# Platine_Diplomarbeit.net
KiCad netlist of a schematic drawn in EAGLE
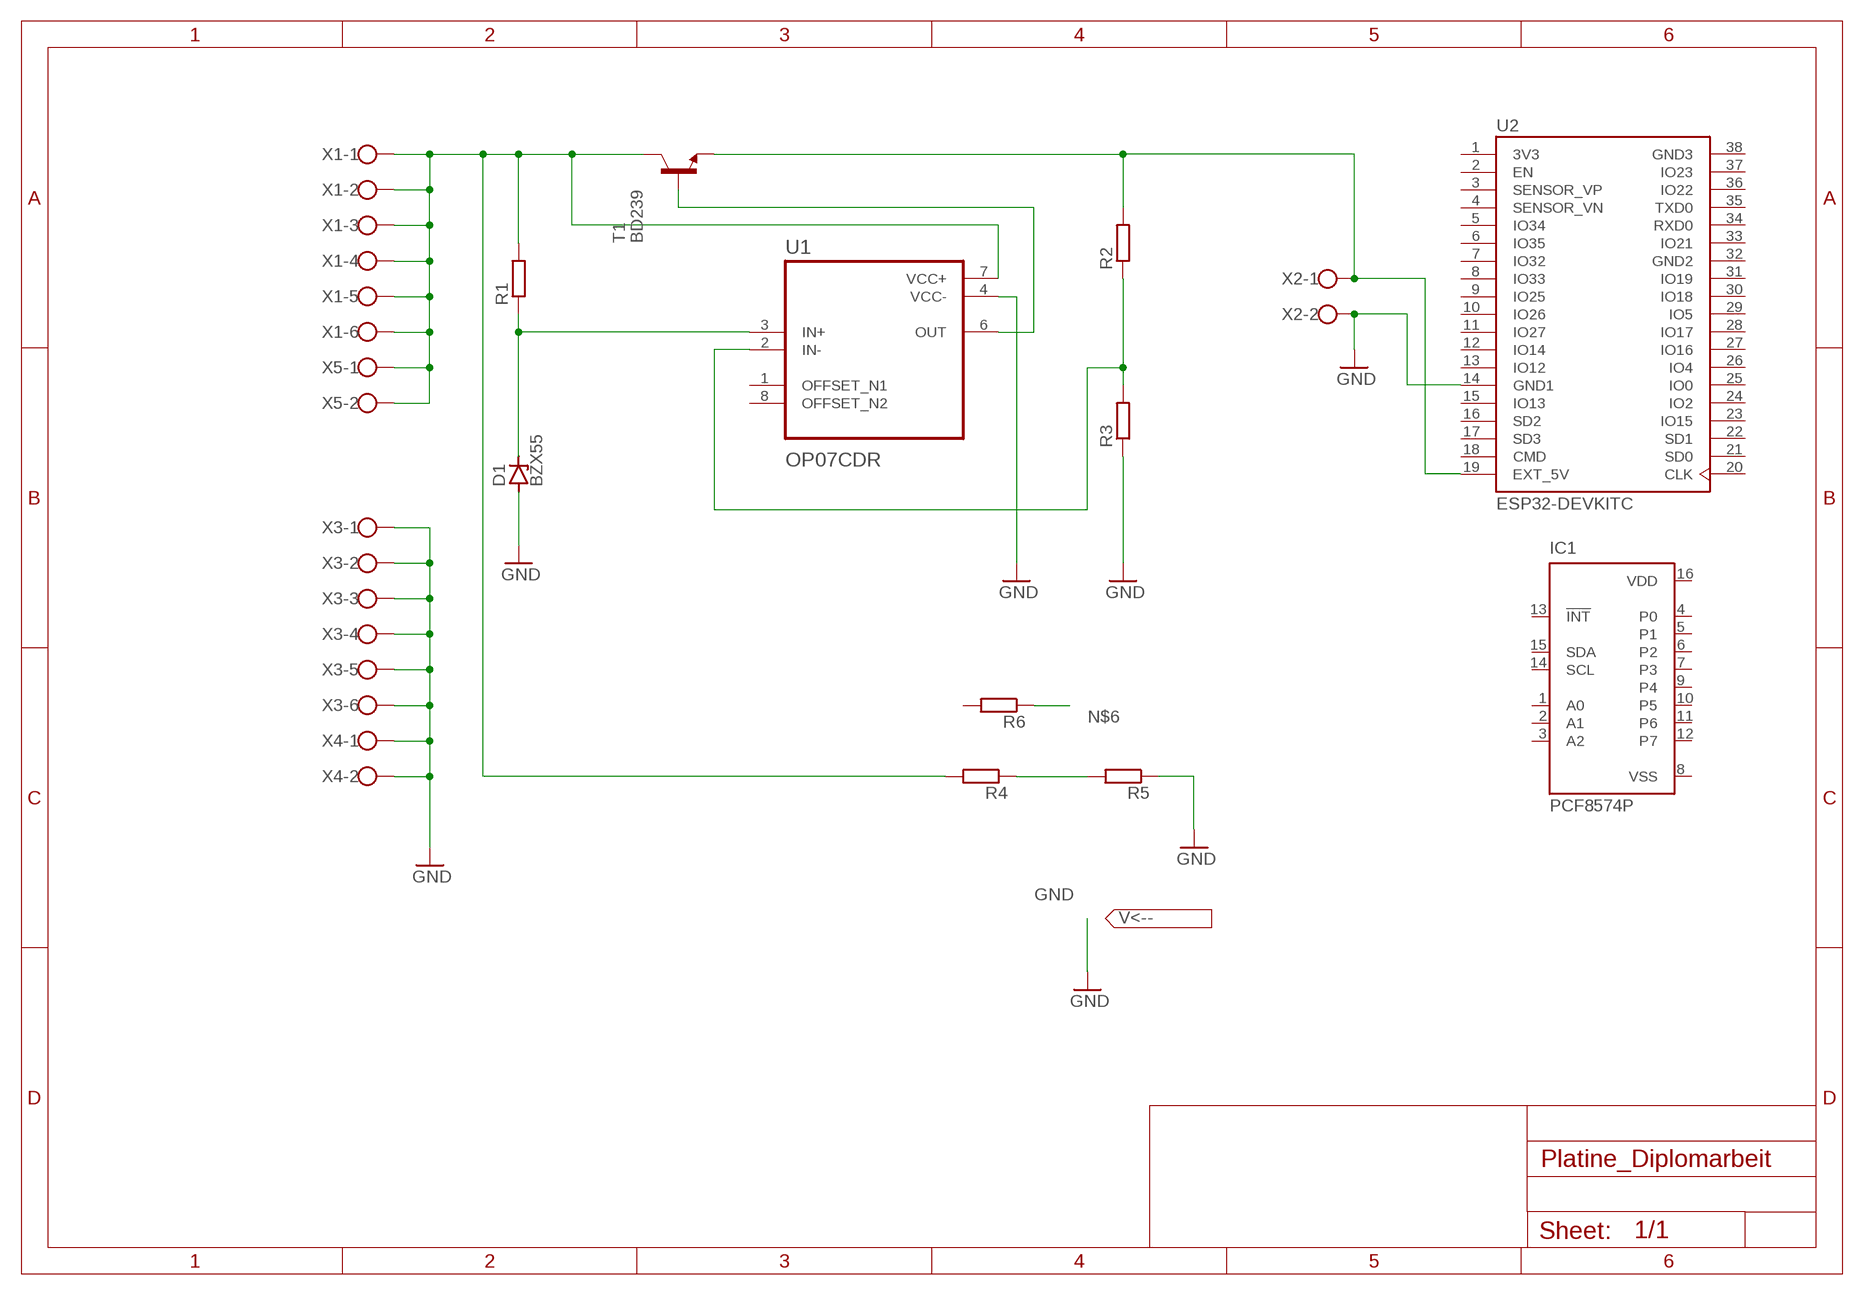
[diagram p0: schematic, sheet 1]

(export (version "E")
  (design (tool "Eeschema 10.0.6"))
  (components
    (comp (ref "D1")
      (value "BZX55")
      (footprint "eagle-import:DO35Z10")
      (libsource (lib "eagle-import") (part "BZX55"))
    )
    (comp (ref "IC1")
      (value "PCF8574P")
      (footprint "eagle-import:DIL16")
      (fields (field (name "MPN") "PCF8574PN"))
      (libsource (lib "eagle-import") (part "PCF8574P"))
    )
    (comp (ref "R1")
      (value "R-EU_0309/12")
      (footprint "eagle-import:0309_12")
      (libsource (lib "eagle-import") (part "R-EU_0309/12"))
    )
    (comp (ref "R2")
      (value "R-EU_0309/12")
      (footprint "eagle-import:0309_12")
      (libsource (lib "eagle-import") (part "R-EU_0309/12"))
    )
    (comp (ref "R3")
      (value "R-EU_0309/12")
      (footprint "eagle-import:0309_12")
      (libsource (lib "eagle-import") (part "R-EU_0309/12"))
    )
    (comp (ref "R4")
      (value "R-EU_0309/12")
      (footprint "eagle-import:0309_12")
      (libsource (lib "eagle-import") (part "R-EU_0309/12"))
    )
    (comp (ref "R5")
      (value "R-EU_0309/12")
      (footprint "eagle-import:0309_12")
      (libsource (lib "eagle-import") (part "R-EU_0309/12"))
    )
    (comp (ref "R6")
      (value "R-EU_0309/12")
      (footprint "eagle-import:0309_12")
      (libsource (lib "eagle-import") (part "R-EU_0309/12"))
    )
    (comp (ref "T1")
      (value "BD239")
      (footprint "eagle-import:TO220")
      (libsource (lib "eagle-import") (part "BD239"))
    )
    (comp (ref "U1")
      (value "OP07CDR")
      (footprint "eagle-import:SOIC127P599X175-8N")
      (fields (field (name "MF") "Texas Instruments"))
      (libsource (lib "eagle-import") (part "OP07CDR"))
    )
    (comp (ref "U2")
      (value "ESP32-DEVKITC")
      (footprint "eagle-import:MODULE_ESP32-DEVKITC")
      (fields (field (name "MF") "Olimex LTD"))
      (libsource (lib "eagle-import") (part "ESP32-DEVKITC"))
    )
    (comp (ref "X1")
      (value "W237-6")
      (footprint "eagle-import:W237-6")
      (libsource (lib "eagle-import") (part "W237-6"))
    )
    (comp (ref "X2")
      (value "W237-102")
      (footprint "eagle-import:W237-102")
      (fields (field (name "MPN") "237-102"))
      (libsource (lib "eagle-import") (part "W237-102"))
    )
    (comp (ref "X3")
      (value "W237-6")
      (footprint "eagle-import:W237-6")
      (libsource (lib "eagle-import") (part "W237-6"))
    )
    (comp (ref "X4")
      (value "W237-102")
      (footprint "eagle-import:W237-102")
      (fields (field (name "MPN") "237-102"))
      (libsource (lib "eagle-import") (part "W237-102"))
    )
    (comp (ref "X5")
      (value "W237-102")
      (footprint "eagle-import:W237-102")
      (fields (field (name "MPN") "237-102"))
      (libsource (lib "eagle-import") (part "W237-102"))
    )
  )
  (nets
    (net (code "1") (name "/3V3") (class "Default")
      (node (ref "U2") (pin "1") (pinfunction "3V3_1") (pintype "power_in"))
    )
    (net (code "2") (name "/GND2") (class "Default")
      (node (ref "U2") (pin "32") (pinfunction "GND2_32") (pintype "power_in"))
    )
    (net (code "3") (name "/GND3") (class "Default")
      (node (ref "U2") (pin "38") (pinfunction "GND3_38") (pintype "power_in"))
    )
    (net (code "4") (name "/N$6") (class "Default")
      (node (ref "R6") (pin "1") (pinfunction "1_1") (pintype "passive"))
    )
    (net (code "5") (name "/VDD") (class "Default")
      (node (ref "IC1") (pin "16") (pinfunction "VDD_16") (pintype "power_in"))
    )
    (net (code "6") (name "/VSS") (class "Default")
      (node (ref "IC1") (pin "8") (pinfunction "VSS_8") (pintype "power_in"))
    )
    (net (code "7") (name "GND") (class "Default")
      (node (ref "D1") (pin "A") (pinfunction "A_A") (pintype "passive"))
      (node (ref "R3") (pin "1") (pinfunction "1_1") (pintype "passive"))
      (node (ref "R5") (pin "1") (pinfunction "1_1") (pintype "passive"))
      (node (ref "U1") (pin "4") (pinfunction "VCC-_4") (pintype "power_in"))
      (node (ref "U2") (pin "14") (pinfunction "GND1_14") (pintype "power_in"))
      (node (ref "X2") (pin "2") (pinfunction "KL_2") (pintype "passive"))
      (node (ref "X3") (pin "1") (pinfunction "KL_1") (pintype "passive"))
      (node (ref "X3") (pin "2") (pinfunction "KL_2") (pintype "passive"))
      (node (ref "X3") (pin "3") (pinfunction "KL_3") (pintype "passive"))
      (node (ref "X3") (pin "4") (pinfunction "KL_4") (pintype "passive"))
      (node (ref "X3") (pin "5") (pinfunction "KL_5") (pintype "passive"))
      (node (ref "X3") (pin "6") (pinfunction "KL_6") (pintype "passive"))
      (node (ref "X4") (pin "1") (pinfunction "KL_1") (pintype "passive"))
      (node (ref "X4") (pin "2") (pinfunction "KL_2") (pintype "passive"))
    )
    (net (code "8") (name "Net-(R4-Pad1)") (class "Default")
      (node (ref "R4") (pin "1") (pinfunction "1_1") (pintype "passive"))
      (node (ref "R5") (pin "2") (pinfunction "2_2") (pintype "passive"))
    )
    (net (code "9") (name "Net-(T1-B)") (class "Default")
      (node (ref "T1") (pin "1") (pinfunction "B_1") (pintype "passive"))
      (node (ref "U1") (pin "6") (pinfunction "OUT_6") (pintype "output"))
    )
    (net (code "10") (name "Net-(T1-C)") (class "Default")
      (node (ref "R1") (pin "2") (pinfunction "2_2") (pintype "passive"))
      (node (ref "R4") (pin "2") (pinfunction "2_2") (pintype "passive"))
      (node (ref "T1") (pin "2") (pinfunction "C_2") (pintype "passive"))
      (node (ref "U1") (pin "7") (pinfunction "VCC+_7") (pintype "power_in"))
      (node (ref "X1") (pin "1") (pinfunction "KL_1") (pintype "passive"))
      (node (ref "X1") (pin "2") (pinfunction "KL_2") (pintype "passive"))
      (node (ref "X1") (pin "3") (pinfunction "KL_3") (pintype "passive"))
      (node (ref "X1") (pin "4") (pinfunction "KL_4") (pintype "passive"))
      (node (ref "X1") (pin "5") (pinfunction "KL_5") (pintype "passive"))
      (node (ref "X1") (pin "6") (pinfunction "KL_6") (pintype "passive"))
      (node (ref "X5") (pin "1") (pinfunction "KL_1") (pintype "passive"))
      (node (ref "X5") (pin "2") (pinfunction "KL_2") (pintype "passive"))
    )
    (net (code "11") (name "Net-(T1-E)") (class "Default")
      (node (ref "R2") (pin "2") (pinfunction "2_2") (pintype "passive"))
      (node (ref "T1") (pin "3") (pinfunction "E_3") (pintype "passive"))
      (node (ref "U2") (pin "19") (pinfunction "EXT_5V_19") (pintype "power_in"))
      (node (ref "X2") (pin "1") (pinfunction "KL_1") (pintype "passive"))
    )
    (net (code "12") (name "Net-(U1-IN+)") (class "Default")
      (node (ref "D1") (pin "C") (pinfunction "C_C") (pintype "passive"))
      (node (ref "R1") (pin "1") (pinfunction "1_1") (pintype "passive"))
      (node (ref "U1") (pin "3") (pinfunction "IN+_3") (pintype "input"))
    )
    (net (code "13") (name "Net-(U1-IN-)") (class "Default")
      (node (ref "R2") (pin "1") (pinfunction "1_1") (pintype "passive"))
      (node (ref "R3") (pin "2") (pinfunction "2_2") (pintype "passive"))
      (node (ref "U1") (pin "2") (pinfunction "IN-_2") (pintype "input"))
    )
    (net (code "14") (name "unconnected-(IC1-A0-Pad1)") (class "Default")
      (node (ref "IC1") (pin "1") (pinfunction "A0_1") (pintype "input"))
    )
    (net (code "15") (name "unconnected-(IC1-A1-Pad2)") (class "Default")
      (node (ref "IC1") (pin "2") (pinfunction "A1_2") (pintype "input"))
    )
    (net (code "16") (name "unconnected-(IC1-A2-Pad3)") (class "Default")
      (node (ref "IC1") (pin "3") (pinfunction "A2_3") (pintype "input"))
    )
    (net (code "17") (name "unconnected-(IC1-P0-Pad4)") (class "Default")
      (node (ref "IC1") (pin "4") (pinfunction "P0_4") (pintype "bidirectional"))
    )
    (net (code "18") (name "unconnected-(IC1-P1-Pad5)") (class "Default")
      (node (ref "IC1") (pin "5") (pinfunction "P1_5") (pintype "bidirectional"))
    )
    (net (code "19") (name "unconnected-(IC1-P2-Pad6)") (class "Default")
      (node (ref "IC1") (pin "6") (pinfunction "P2_6") (pintype "bidirectional"))
    )
    (net (code "20") (name "unconnected-(IC1-P3-Pad7)") (class "Default")
      (node (ref "IC1") (pin "7") (pinfunction "P3_7") (pintype "bidirectional"))
    )
    (net (code "21") (name "unconnected-(IC1-P4-Pad9)") (class "Default")
      (node (ref "IC1") (pin "9") (pinfunction "P4_9") (pintype "bidirectional"))
    )
    (net (code "22") (name "unconnected-(IC1-P5-Pad10)") (class "Default")
      (node (ref "IC1") (pin "10") (pinfunction "P5_10") (pintype "bidirectional"))
    )
    (net (code "23") (name "unconnected-(IC1-P6-Pad11)") (class "Default")
      (node (ref "IC1") (pin "11") (pinfunction "P6_11") (pintype "bidirectional"))
    )
    (net (code "24") (name "unconnected-(IC1-P7-Pad12)") (class "Default")
      (node (ref "IC1") (pin "12") (pinfunction "P7_12") (pintype "bidirectional"))
    )
    (net (code "25") (name "unconnected-(IC1-SCL-Pad14)") (class "Default")
      (node (ref "IC1") (pin "14") (pinfunction "SCL_14") (pintype "input"))
    )
    (net (code "26") (name "unconnected-(IC1-SDA-Pad15)") (class "Default")
      (node (ref "IC1") (pin "15") (pinfunction "SDA_15") (pintype "bidirectional"))
    )
    (net (code "27") (name "unconnected-(IC1-~{INT}-Pad13)") (class "Default")
      (node (ref "IC1") (pin "13") (pinfunction "~{INT}_13") (pintype "output"))
    )
    (net (code "28") (name "unconnected-(R6-Pad2)") (class "Default")
      (node (ref "R6") (pin "2") (pinfunction "2_2") (pintype "passive"))
    )
    (net (code "29") (name "unconnected-(U1-OFFSET_N1-Pad1)") (class "Default")
      (node (ref "U1") (pin "1") (pinfunction "OFFSET_N1_1") (pintype "bidirectional"))
    )
    (net (code "30") (name "unconnected-(U1-OFFSET_N2-Pad8)") (class "Default")
      (node (ref "U1") (pin "8") (pinfunction "OFFSET_N2_8") (pintype "bidirectional"))
    )
    (net (code "31") (name "unconnected-(U2-CLK-Pad20)") (class "Default")
      (node (ref "U2") (pin "20") (pinfunction "CLK_20") (pintype "input"))
    )
    (net (code "32") (name "unconnected-(U2-CMD-Pad18)") (class "Default")
      (node (ref "U2") (pin "18") (pinfunction "CMD_18") (pintype "bidirectional"))
    )
    (net (code "33") (name "unconnected-(U2-EN-Pad2)") (class "Default")
      (node (ref "U2") (pin "2") (pinfunction "EN_2") (pintype "input"))
    )
    (net (code "34") (name "unconnected-(U2-IO0-Pad25)") (class "Default")
      (node (ref "U2") (pin "25") (pinfunction "IO0_25") (pintype "bidirectional"))
    )
    (net (code "35") (name "unconnected-(U2-IO2-Pad24)") (class "Default")
      (node (ref "U2") (pin "24") (pinfunction "IO2_24") (pintype "bidirectional"))
    )
    (net (code "36") (name "unconnected-(U2-IO4-Pad26)") (class "Default")
      (node (ref "U2") (pin "26") (pinfunction "IO4_26") (pintype "bidirectional"))
    )
    (net (code "37") (name "unconnected-(U2-IO5-Pad29)") (class "Default")
      (node (ref "U2") (pin "29") (pinfunction "IO5_29") (pintype "bidirectional"))
    )
    (net (code "38") (name "unconnected-(U2-IO12-Pad13)") (class "Default")
      (node (ref "U2") (pin "13") (pinfunction "IO12_13") (pintype "bidirectional"))
    )
    (net (code "39") (name "unconnected-(U2-IO13-Pad15)") (class "Default")
      (node (ref "U2") (pin "15") (pinfunction "IO13_15") (pintype "bidirectional"))
    )
    (net (code "40") (name "unconnected-(U2-IO14-Pad12)") (class "Default")
      (node (ref "U2") (pin "12") (pinfunction "IO14_12") (pintype "bidirectional"))
    )
    (net (code "41") (name "unconnected-(U2-IO15-Pad23)") (class "Default")
      (node (ref "U2") (pin "23") (pinfunction "IO15_23") (pintype "bidirectional"))
    )
    (net (code "42") (name "unconnected-(U2-IO16-Pad27)") (class "Default")
      (node (ref "U2") (pin "27") (pinfunction "IO16_27") (pintype "bidirectional"))
    )
    (net (code "43") (name "unconnected-(U2-IO17-Pad28)") (class "Default")
      (node (ref "U2") (pin "28") (pinfunction "IO17_28") (pintype "bidirectional"))
    )
    (net (code "44") (name "unconnected-(U2-IO18-Pad30)") (class "Default")
      (node (ref "U2") (pin "30") (pinfunction "IO18_30") (pintype "bidirectional"))
    )
    (net (code "45") (name "unconnected-(U2-IO19-Pad31)") (class "Default")
      (node (ref "U2") (pin "31") (pinfunction "IO19_31") (pintype "bidirectional"))
    )
    (net (code "46") (name "unconnected-(U2-IO21-Pad33)") (class "Default")
      (node (ref "U2") (pin "33") (pinfunction "IO21_33") (pintype "bidirectional"))
    )
    (net (code "47") (name "unconnected-(U2-IO22-Pad36)") (class "Default")
      (node (ref "U2") (pin "36") (pinfunction "IO22_36") (pintype "bidirectional"))
    )
    (net (code "48") (name "unconnected-(U2-IO23-Pad37)") (class "Default")
      (node (ref "U2") (pin "37") (pinfunction "IO23_37") (pintype "bidirectional"))
    )
    (net (code "49") (name "unconnected-(U2-IO25-Pad9)") (class "Default")
      (node (ref "U2") (pin "9") (pinfunction "IO25_9") (pintype "bidirectional"))
    )
    (net (code "50") (name "unconnected-(U2-IO26-Pad10)") (class "Default")
      (node (ref "U2") (pin "10") (pinfunction "IO26_10") (pintype "bidirectional"))
    )
    (net (code "51") (name "unconnected-(U2-IO27-Pad11)") (class "Default")
      (node (ref "U2") (pin "11") (pinfunction "IO27_11") (pintype "bidirectional"))
    )
    (net (code "52") (name "unconnected-(U2-IO32-Pad7)") (class "Default")
      (node (ref "U2") (pin "7") (pinfunction "IO32_7") (pintype "bidirectional"))
    )
    (net (code "53") (name "unconnected-(U2-IO33-Pad8)") (class "Default")
      (node (ref "U2") (pin "8") (pinfunction "IO33_8") (pintype "bidirectional"))
    )
    (net (code "54") (name "unconnected-(U2-IO34-Pad5)") (class "Default")
      (node (ref "U2") (pin "5") (pinfunction "IO34_5") (pintype "bidirectional"))
    )
    (net (code "55") (name "unconnected-(U2-IO35-Pad6)") (class "Default")
      (node (ref "U2") (pin "6") (pinfunction "IO35_6") (pintype "bidirectional"))
    )
    (net (code "56") (name "unconnected-(U2-RXD0-Pad34)") (class "Default")
      (node (ref "U2") (pin "34") (pinfunction "RXD0_34") (pintype "input"))
    )
    (net (code "57") (name "unconnected-(U2-SD0-Pad21)") (class "Default")
      (node (ref "U2") (pin "21") (pinfunction "SD0_21") (pintype "bidirectional"))
    )
    (net (code "58") (name "unconnected-(U2-SD1-Pad22)") (class "Default")
      (node (ref "U2") (pin "22") (pinfunction "SD1_22") (pintype "bidirectional"))
    )
    (net (code "59") (name "unconnected-(U2-SD2-Pad16)") (class "Default")
      (node (ref "U2") (pin "16") (pinfunction "SD2_16") (pintype "bidirectional"))
    )
    (net (code "60") (name "unconnected-(U2-SD3-Pad17)") (class "Default")
      (node (ref "U2") (pin "17") (pinfunction "SD3_17") (pintype "bidirectional"))
    )
    (net (code "61") (name "unconnected-(U2-SENSOR_VN-Pad4)") (class "Default")
      (node (ref "U2") (pin "4") (pinfunction "SENSOR_VN_4") (pintype "input"))
    )
    (net (code "62") (name "unconnected-(U2-SENSOR_VP-Pad3)") (class "Default")
      (node (ref "U2") (pin "3") (pinfunction "SENSOR_VP_3") (pintype "input"))
    )
    (net (code "63") (name "unconnected-(U2-TXD0-Pad35)") (class "Default")
      (node (ref "U2") (pin "35") (pinfunction "TXD0_35") (pintype "output"))
    )
  )
)
